# POWER_CORE.net
KiCad netlist of a schematic drawn in Altium Designer
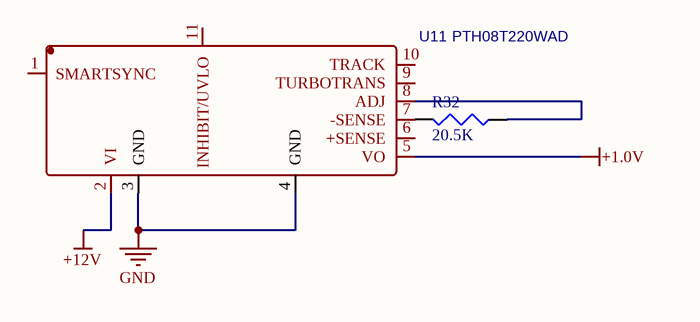
[diagram p0: POWER_CORE.SchDoc]

(export (version "E")
  (design (tool "Eeschema 10.0.6"))
  (components
    (comp (ref "R32")
      (value "20.5K")
      (footprint "J1-0603")
      (description "Resistor")
      (fields (field (name "Comment") "Res3") (field (name "PUBLISHER") "Altium Limited"))
      (libsource (lib "Miscellaneous Devices") (part "Res3"))
    )
    (comp (ref "U11")
      (value "PTH08T220WAD")
      (footprint "PWRM-TH_11P-L23.1-W19.9-P3.17")
      (fields (field (name "BOM_SUPPLIER PART") "C79289") (field (name "CONTRIBUTOR") "LCSC"))
      (libsource (lib "power_chip") (part "PTH08T220WAD"))
    )
  )
  (nets
    (net (code "1") (name "+1.0V") (class "Default")
      (node (ref "U11") (pin "5") (pinfunction "VO_5") (pintype "passive"))
    )
    (net (code "2") (name "+12V") (class "Default")
      (node (ref "U11") (pin "2") (pinfunction "VI_2") (pintype "passive"))
    )
    (net (code "3") (name "GND") (class "Default")
      (node (ref "U11") (pin "3") (pinfunction "GND_3") (pintype "passive"))
      (node (ref "U11") (pin "4") (pinfunction "GND_4") (pintype "passive"))
    )
    (net (code "4") (name "Net-(U11--SENSE)") (class "Default")
      (node (ref "R32") (pin "2") (pinfunction "2_2") (pintype "passive"))
      (node (ref "U11") (pin "7") (pinfunction "-SENSE_7") (pintype "passive"))
    )
    (net (code "5") (name "Net-(U11-ADJ)") (class "Default")
      (node (ref "R32") (pin "1") (pinfunction "1_1") (pintype "passive"))
      (node (ref "U11") (pin "8") (pinfunction "ADJ_8") (pintype "passive"))
    )
    (net (code "6") (name "unconnected-(U11-+SENSE-Pad6)") (class "Default")
      (node (ref "U11") (pin "6") (pinfunction "+SENSE_6") (pintype "passive"))
    )
    (net (code "7") (name "unconnected-(U11-INHIBIT{slash}UVLO-Pad11)") (class "Default")
      (node (ref "U11") (pin "11") (pinfunction "INHIBIT/UVLO_11") (pintype "passive"))
    )
    (net (code "8") (name "unconnected-(U11-SMARTSYNC-Pad1)") (class "Default")
      (node (ref "U11") (pin "1") (pinfunction "SMARTSYNC_1") (pintype "passive"))
    )
    (net (code "9") (name "unconnected-(U11-TRACK-Pad10)") (class "Default")
      (node (ref "U11") (pin "10") (pinfunction "TRACK_10") (pintype "passive"))
    )
    (net (code "10") (name "unconnected-(U11-TURBOTRANS-Pad9)") (class "Default")
      (node (ref "U11") (pin "9") (pinfunction "TURBOTRANS_9") (pintype "passive"))
    )
  )
)
